# Wi07_Adapter.net
KiCad netlist of a schematic drawn in EAGLE
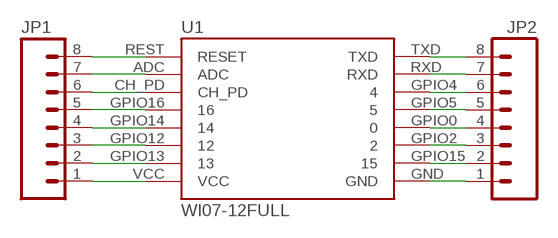
[diagram p0: schematic, sheet 1]

(export (version "E")
  (design (tool "Eeschema 10.0.6"))
  (components
    (comp (ref "JP1")
      (value "M08")
      (footprint "eagle-import:1X08_PIN1_NO_SILK")
      (libsource (lib "eagle-import") (part "M08"))
    )
    (comp (ref "JP2")
      (value "M08")
      (footprint "eagle-import:1X08_PIN1_NO_SILK")
      (libsource (lib "eagle-import") (part "M08"))
    )
    (comp (ref "U1")
      (value "WI07-12FULL")
      (footprint "eagle-import:WI07-12")
      (libsource (lib "eagle-import") (part "WI07-12FULL"))
    )
  )
  (nets
    (net (code "1") (name "Net-(JP1-Pad1)") (class "Default")
      (node (ref "JP1") (pin "1") (pinfunction "1_1") (pintype "passive"))
      (node (ref "U1") (pin "VCC") (pinfunction "VCC_VCC") (pintype "power_in"))
    )
    (net (code "2") (name "Net-(JP1-Pad6)") (class "Default")
      (node (ref "JP1") (pin "6") (pinfunction "6_6") (pintype "passive"))
      (node (ref "U1") (pin "CH_PD") (pinfunction "CH_PD_CH_PD") (pintype "input"))
    )
    (net (code "3") (name "Net-(JP1-Pad7)") (class "Default")
      (node (ref "JP1") (pin "7") (pinfunction "7_7") (pintype "passive"))
      (node (ref "U1") (pin "ADC") (pinfunction "ADC_ADC") (pintype "input"))
    )
    (net (code "4") (name "Net-(JP2-Pad1)") (class "Default")
      (node (ref "JP2") (pin "1") (pinfunction "1_1") (pintype "passive"))
      (node (ref "U1") (pin "GND") (pinfunction "GND_GND") (pintype "power_in"))
    )
    (net (code "5") (name "Net-(JP2-Pad7)") (class "Default")
      (node (ref "JP2") (pin "7") (pinfunction "7_7") (pintype "passive"))
      (node (ref "U1") (pin "RXD") (pinfunction "RXD_RXD") (pintype "output"))
    )
    (net (code "6") (name "Net-(JP2-Pad8)") (class "Default")
      (node (ref "JP2") (pin "8") (pinfunction "8_8") (pintype "passive"))
      (node (ref "U1") (pin "TXD") (pinfunction "TXD_TXD") (pintype "input"))
    )
    (net (code "7") (name "Net-(U1-0)") (class "Default")
      (node (ref "JP2") (pin "4") (pinfunction "4_4") (pintype "passive"))
      (node (ref "U1") (pin "GPIO0") (pinfunction "0_GPIO0") (pintype "bidirectional"))
    )
    (net (code "8") (name "Net-(U1-2)") (class "Default")
      (node (ref "JP2") (pin "3") (pinfunction "3_3") (pintype "passive"))
      (node (ref "U1") (pin "GPIO2") (pinfunction "2_GPIO2") (pintype "bidirectional"))
    )
    (net (code "9") (name "Net-(U1-4)") (class "Default")
      (node (ref "JP2") (pin "6") (pinfunction "6_6") (pintype "passive"))
      (node (ref "U1") (pin "GPIO4") (pinfunction "4_GPIO4") (pintype "bidirectional"))
    )
    (net (code "10") (name "Net-(U1-5)") (class "Default")
      (node (ref "JP2") (pin "5") (pinfunction "5_5") (pintype "passive"))
      (node (ref "U1") (pin "GPIO5") (pinfunction "5_GPIO5") (pintype "bidirectional"))
    )
    (net (code "11") (name "Net-(U1-12)") (class "Default")
      (node (ref "JP1") (pin "3") (pinfunction "3_3") (pintype "passive"))
      (node (ref "U1") (pin "GPIO12") (pinfunction "12_GPIO12") (pintype "bidirectional"))
    )
    (net (code "12") (name "Net-(U1-13)") (class "Default")
      (node (ref "JP1") (pin "2") (pinfunction "2_2") (pintype "passive"))
      (node (ref "U1") (pin "GPIO13") (pinfunction "13_GPIO13") (pintype "bidirectional"))
    )
    (net (code "13") (name "Net-(U1-14)") (class "Default")
      (node (ref "JP1") (pin "4") (pinfunction "4_4") (pintype "passive"))
      (node (ref "U1") (pin "GPIO14") (pinfunction "14_GPIO14") (pintype "bidirectional"))
    )
    (net (code "14") (name "Net-(U1-15)") (class "Default")
      (node (ref "JP2") (pin "2") (pinfunction "2_2") (pintype "passive"))
      (node (ref "U1") (pin "GPIO15") (pinfunction "15_GPIO15") (pintype "bidirectional"))
    )
    (net (code "15") (name "Net-(U1-16)") (class "Default")
      (node (ref "JP1") (pin "5") (pinfunction "5_5") (pintype "passive"))
      (node (ref "U1") (pin "GPIO16") (pinfunction "16_GPIO16") (pintype "bidirectional"))
    )
    (net (code "16") (name "Net-(U1-RESET)") (class "Default")
      (node (ref "JP1") (pin "8") (pinfunction "8_8") (pintype "passive"))
      (node (ref "U1") (pin "REST") (pinfunction "RESET_REST") (pintype "input"))
    )
  )
)
